# RPiSoC_Shield.net
KiCad netlist of a schematic drawn in EAGLE
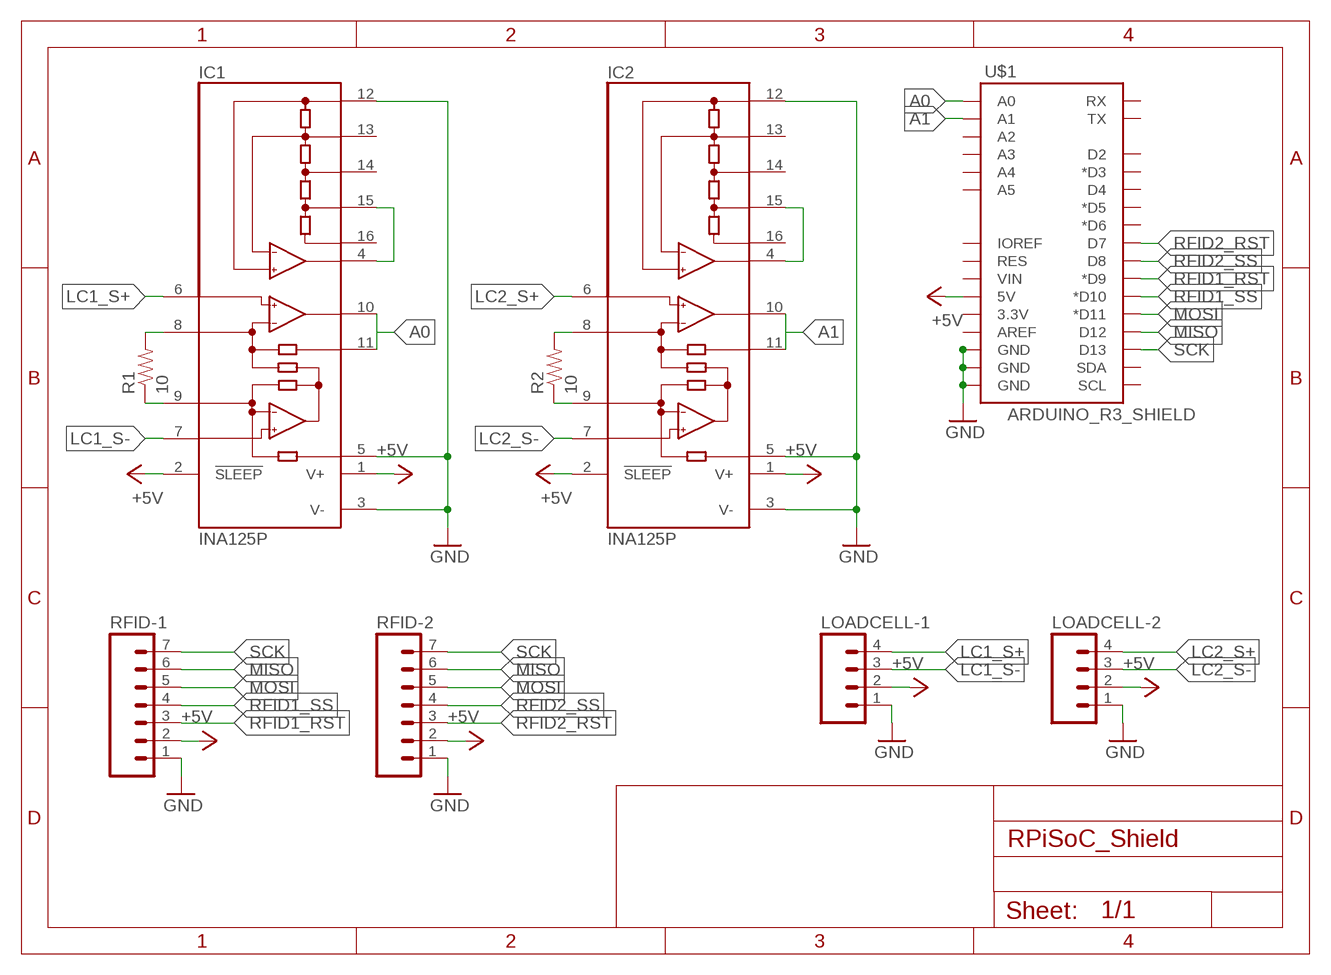
[diagram p0: schematic, sheet 1]

(export (version "E")
  (design (tool "Eeschema 10.0.6"))
  (components
    (comp (ref "IC1")
      (value "INA125P")
      (footprint "eagle-import:DIL16")
      (fields (field (name "MF") "TEXAS INSTRUMENT CONNECTORS"))
      (libsource (lib "eagle-import") (part "INA125P"))
    )
    (comp (ref "IC2")
      (value "INA125P")
      (footprint "eagle-import:DIL16")
      (fields (field (name "MF") "TEXAS INSTRUMENT CONNECTORS"))
      (libsource (lib "eagle-import") (part "INA125P"))
    )
    (comp (ref "LOADCELL-1")
      (value "M04PTH")
      (footprint "eagle-import:1X04")
      (libsource (lib "eagle-import") (part "M04PTH"))
    )
    (comp (ref "LOADCELL-2")
      (value "M04PTH")
      (footprint "eagle-import:1X04")
      (libsource (lib "eagle-import") (part "M04PTH"))
    )
    (comp (ref "R1")
      (value "10")
      (footprint "eagle-import:AXIAL-0.3EZ")
      (libsource (lib "eagle-import") (part "RESISTOREZ"))
    )
    (comp (ref "R2")
      (value "10")
      (footprint "eagle-import:AXIAL-0.3EZ")
      (libsource (lib "eagle-import") (part "RESISTOREZ"))
    )
    (comp (ref "RFID-1")
      (value "M07")
      (footprint "eagle-import:1X07")
      (libsource (lib "eagle-import") (part "M07"))
    )
    (comp (ref "RFID-2")
      (value "M07")
      (footprint "eagle-import:1X07")
      (libsource (lib "eagle-import") (part "M07"))
    )
    (comp (ref "U$1")
      (value "ARDUINO_R3_SHIELD")
      (footprint "eagle-import:UNO_R3_SHIELD")
      (libsource (lib "eagle-import") (part "ARDUINO_R3_SHIELD"))
    )
  )
  (nets
    (net (code "1") (name "+5V") (class "Default")
      (node (ref "IC1") (pin "1") (pinfunction "V+_1") (pintype "power_in"))
      (node (ref "IC1") (pin "2") (pinfunction "~{SLEEP}_2") (pintype "input"))
      (node (ref "IC2") (pin "1") (pinfunction "V+_1") (pintype "power_in"))
      (node (ref "IC2") (pin "2") (pinfunction "~{SLEEP}_2") (pintype "input"))
      (node (ref "LOADCELL-1") (pin "2") (pinfunction "2_2") (pintype "passive"))
      (node (ref "LOADCELL-2") (pin "2") (pinfunction "2_2") (pintype "passive"))
      (node (ref "RFID-1") (pin "2") (pinfunction "2_2") (pintype "passive"))
      (node (ref "RFID-2") (pin "2") (pinfunction "2_2") (pintype "passive"))
      (node (ref "U$1") (pin "5V") (pinfunction "5V_5V") (pintype "bidirectional"))
    )
    (net (code "2") (name "A0") (class "Default")
      (node (ref "IC1") (pin "10") (pinfunction "OUT_10") (pintype "output"))
      (node (ref "IC1") (pin "11") (pinfunction "SENSE_11") (pintype "passive"))
      (node (ref "U$1") (pin "A0") (pinfunction "A0_A0") (pintype "bidirectional"))
    )
    (net (code "3") (name "A1") (class "Default")
      (node (ref "IC2") (pin "10") (pinfunction "OUT_10") (pintype "output"))
      (node (ref "IC2") (pin "11") (pinfunction "SENSE_11") (pintype "passive"))
      (node (ref "U$1") (pin "A1") (pinfunction "A1_A1") (pintype "bidirectional"))
    )
    (net (code "4") (name "GND") (class "Default")
      (node (ref "IC1") (pin "12") (pinfunction "REFCOM_12") (pintype "passive"))
      (node (ref "IC1") (pin "3") (pinfunction "V-_3") (pintype "power_in"))
      (node (ref "IC1") (pin "5") (pinfunction "REF_5") (pintype "passive"))
      (node (ref "IC2") (pin "12") (pinfunction "REFCOM_12") (pintype "passive"))
      (node (ref "IC2") (pin "3") (pinfunction "V-_3") (pintype "power_in"))
      (node (ref "IC2") (pin "5") (pinfunction "REF_5") (pintype "passive"))
      (node (ref "LOADCELL-1") (pin "1") (pinfunction "1_1") (pintype "passive"))
      (node (ref "LOADCELL-2") (pin "1") (pinfunction "1_1") (pintype "passive"))
      (node (ref "RFID-1") (pin "1") (pinfunction "1_1") (pintype "passive"))
      (node (ref "RFID-2") (pin "1") (pinfunction "1_1") (pintype "passive"))
      (node (ref "U$1") (pin "GND@0") (pinfunction "GND_GND@0") (pintype "bidirectional"))
      (node (ref "U$1") (pin "GND@1") (pinfunction "GND_GND@1") (pintype "bidirectional"))
      (node (ref "U$1") (pin "GND@2") (pinfunction "GND_GND@2") (pintype "bidirectional"))
    )
    (net (code "5") (name "LC1_S+") (class "Default")
      (node (ref "IC1") (pin "6") (pinfunction "+IN_6") (pintype "input"))
      (node (ref "LOADCELL-1") (pin "4") (pinfunction "4_4") (pintype "passive"))
    )
    (net (code "6") (name "LC1_S-") (class "Default")
      (node (ref "IC1") (pin "7") (pinfunction "-IN_7") (pintype "input"))
      (node (ref "LOADCELL-1") (pin "3") (pinfunction "3_3") (pintype "passive"))
    )
    (net (code "7") (name "LC2_S+") (class "Default")
      (node (ref "IC2") (pin "6") (pinfunction "+IN_6") (pintype "input"))
      (node (ref "LOADCELL-2") (pin "4") (pinfunction "4_4") (pintype "passive"))
    )
    (net (code "8") (name "LC2_S-") (class "Default")
      (node (ref "IC2") (pin "7") (pinfunction "-IN_7") (pintype "input"))
      (node (ref "LOADCELL-2") (pin "3") (pinfunction "3_3") (pintype "passive"))
    )
    (net (code "9") (name "MISO") (class "Default")
      (node (ref "RFID-1") (pin "6") (pinfunction "6_6") (pintype "passive"))
      (node (ref "RFID-2") (pin "6") (pinfunction "6_6") (pintype "passive"))
      (node (ref "U$1") (pin "D12") (pinfunction "D12_D12") (pintype "bidirectional"))
    )
    (net (code "10") (name "MOSI") (class "Default")
      (node (ref "RFID-1") (pin "5") (pinfunction "5_5") (pintype "passive"))
      (node (ref "RFID-2") (pin "5") (pinfunction "5_5") (pintype "passive"))
      (node (ref "U$1") (pin "D11") (pinfunction "*D11_D11") (pintype "bidirectional"))
    )
    (net (code "11") (name "Net-(IC1-REF5)") (class "Default")
      (node (ref "IC1") (pin "15") (pinfunction "REF5_15") (pintype "output"))
      (node (ref "IC1") (pin "4") (pinfunction "REFOUT_4") (pintype "output"))
    )
    (net (code "12") (name "Net-(IC2-REF5)") (class "Default")
      (node (ref "IC2") (pin "15") (pinfunction "REF5_15") (pintype "output"))
      (node (ref "IC2") (pin "4") (pinfunction "REFOUT_4") (pintype "output"))
    )
    (net (code "13") (name "Net-(R1-1)") (class "Default")
      (node (ref "IC1") (pin "9") (pinfunction "RG_9") (pintype "passive"))
      (node (ref "R1") (pin "P$1") (pinfunction "1_P$1") (pintype "passive"))
    )
    (net (code "14") (name "Net-(R1-2)") (class "Default")
      (node (ref "IC1") (pin "8") (pinfunction "RG_8") (pintype "passive"))
      (node (ref "R1") (pin "P$2") (pinfunction "2_P$2") (pintype "passive"))
    )
    (net (code "15") (name "Net-(R2-1)") (class "Default")
      (node (ref "IC2") (pin "9") (pinfunction "RG_9") (pintype "passive"))
      (node (ref "R2") (pin "P$1") (pinfunction "1_P$1") (pintype "passive"))
    )
    (net (code "16") (name "Net-(R2-2)") (class "Default")
      (node (ref "IC2") (pin "8") (pinfunction "RG_8") (pintype "passive"))
      (node (ref "R2") (pin "P$2") (pinfunction "2_P$2") (pintype "passive"))
    )
    (net (code "17") (name "RFID1_RST") (class "Default")
      (node (ref "RFID-1") (pin "3") (pinfunction "3_3") (pintype "passive"))
      (node (ref "U$1") (pin "D9") (pinfunction "*D9_D9") (pintype "bidirectional"))
    )
    (net (code "18") (name "RFID1_SS") (class "Default")
      (node (ref "RFID-1") (pin "4") (pinfunction "4_4") (pintype "passive"))
      (node (ref "U$1") (pin "D10") (pinfunction "*D10_D10") (pintype "bidirectional"))
    )
    (net (code "19") (name "RFID2_RST") (class "Default")
      (node (ref "RFID-2") (pin "3") (pinfunction "3_3") (pintype "passive"))
      (node (ref "U$1") (pin "D7") (pinfunction "D7_D7") (pintype "bidirectional"))
    )
    (net (code "20") (name "RFID2_SS") (class "Default")
      (node (ref "RFID-2") (pin "4") (pinfunction "4_4") (pintype "passive"))
      (node (ref "U$1") (pin "D8") (pinfunction "D8_D8") (pintype "bidirectional"))
    )
    (net (code "21") (name "SCK") (class "Default")
      (node (ref "RFID-1") (pin "7") (pinfunction "7_7") (pintype "passive"))
      (node (ref "RFID-2") (pin "7") (pinfunction "7_7") (pintype "passive"))
      (node (ref "U$1") (pin "D13") (pinfunction "D13_D13") (pintype "bidirectional"))
    )
    (net (code "22") (name "unconnected-(IC1-REF2.5-Pad14)") (class "Default")
      (node (ref "IC1") (pin "14") (pinfunction "REF2.5_14") (pintype "output"))
    )
    (net (code "23") (name "unconnected-(IC1-REF10-Pad16)") (class "Default")
      (node (ref "IC1") (pin "16") (pinfunction "REF10_16") (pintype "output"))
    )
    (net (code "24") (name "unconnected-(IC1-REFBG-Pad13)") (class "Default")
      (node (ref "IC1") (pin "13") (pinfunction "REFBG_13") (pintype "output"))
    )
    (net (code "25") (name "unconnected-(IC2-REF2.5-Pad14)") (class "Default")
      (node (ref "IC2") (pin "14") (pinfunction "REF2.5_14") (pintype "output"))
    )
    (net (code "26") (name "unconnected-(IC2-REF10-Pad16)") (class "Default")
      (node (ref "IC2") (pin "16") (pinfunction "REF10_16") (pintype "output"))
    )
    (net (code "27") (name "unconnected-(IC2-REFBG-Pad13)") (class "Default")
      (node (ref "IC2") (pin "13") (pinfunction "REFBG_13") (pintype "output"))
    )
    (net (code "28") (name "unconnected-(U$1-*D3-PadD3)") (class "Default")
      (node (ref "U$1") (pin "D3") (pinfunction "*D3_D3") (pintype "bidirectional"))
    )
    (net (code "29") (name "unconnected-(U$1-*D5-PadD5)") (class "Default")
      (node (ref "U$1") (pin "D5") (pinfunction "*D5_D5") (pintype "bidirectional"))
    )
    (net (code "30") (name "unconnected-(U$1-*D6-PadD6)") (class "Default")
      (node (ref "U$1") (pin "D6") (pinfunction "*D6_D6") (pintype "bidirectional"))
    )
    (net (code "31") (name "unconnected-(U$1-Pad3.3V)") (class "Default")
      (node (ref "U$1") (pin "3.3V") (pinfunction "3.3V_3.3V") (pintype "bidirectional"))
    )
    (net (code "32") (name "unconnected-(U$1-PadA2)") (class "Default")
      (node (ref "U$1") (pin "A2") (pinfunction "A2_A2") (pintype "bidirectional"))
    )
    (net (code "33") (name "unconnected-(U$1-PadA3)") (class "Default")
      (node (ref "U$1") (pin "A3") (pinfunction "A3_A3") (pintype "bidirectional"))
    )
    (net (code "34") (name "unconnected-(U$1-PadA4)") (class "Default")
      (node (ref "U$1") (pin "A4") (pinfunction "A4_A4") (pintype "bidirectional"))
    )
    (net (code "35") (name "unconnected-(U$1-PadA5)") (class "Default")
      (node (ref "U$1") (pin "A5") (pinfunction "A5_A5") (pintype "bidirectional"))
    )
    (net (code "36") (name "unconnected-(U$1-PadAREF)") (class "Default")
      (node (ref "U$1") (pin "AREF") (pinfunction "AREF_AREF") (pintype "bidirectional"))
    )
    (net (code "37") (name "unconnected-(U$1-PadD2)") (class "Default")
      (node (ref "U$1") (pin "D2") (pinfunction "D2_D2") (pintype "bidirectional"))
    )
    (net (code "38") (name "unconnected-(U$1-PadD4)") (class "Default")
      (node (ref "U$1") (pin "D4") (pinfunction "D4_D4") (pintype "bidirectional"))
    )
    (net (code "39") (name "unconnected-(U$1-PadIOREF)") (class "Default")
      (node (ref "U$1") (pin "IOREF") (pinfunction "IOREF_IOREF") (pintype "bidirectional"))
    )
    (net (code "40") (name "unconnected-(U$1-PadRES)") (class "Default")
      (node (ref "U$1") (pin "RES") (pinfunction "RES_RES") (pintype "bidirectional"))
    )
    (net (code "41") (name "unconnected-(U$1-PadRX)") (class "Default")
      (node (ref "U$1") (pin "RX") (pinfunction "RX_RX") (pintype "bidirectional"))
    )
    (net (code "42") (name "unconnected-(U$1-PadSCL)") (class "Default")
      (node (ref "U$1") (pin "SCL") (pinfunction "SCL_SCL") (pintype "bidirectional"))
    )
    (net (code "43") (name "unconnected-(U$1-PadSDA)") (class "Default")
      (node (ref "U$1") (pin "SDA") (pinfunction "SDA_SDA") (pintype "bidirectional"))
    )
    (net (code "44") (name "unconnected-(U$1-PadTX)") (class "Default")
      (node (ref "U$1") (pin "TX") (pinfunction "TX_TX") (pintype "bidirectional"))
    )
    (net (code "45") (name "unconnected-(U$1-PadVIN)") (class "Default")
      (node (ref "U$1") (pin "VIN") (pinfunction "VIN_VIN") (pintype "bidirectional"))
    )
  )
)
